# connector.net
KiCad netlist of a schematic drawn in Altium Designer
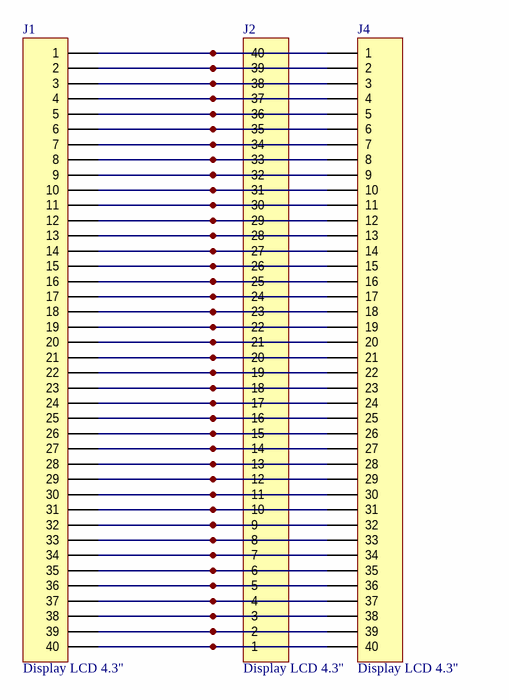
[diagram p0: connector.SchDoc]

(export (version "E")
  (design (tool "Eeschema 10.0.6"))
  (components
    (comp (ref "J1")
      (value "Display LCD 4.3''")
      (footprint "fcc-zif_40pin_0.5mm")
      (description "40-pin, 0.5mm, SMT, ZIF, Horizontal, Top Contact (WE 68714014022; Molex: 54104-4031)")
      (fields (field (name "PUBLISHER") "Altium Limited"))
      (libsource (lib "") (part "Header 40_1"))
    )
    (comp (ref "J2")
      (value "Display LCD 4.3''")
      (footprint "fcc-zif_40pin_0.5mm")
      (description "40-pin, 0.5mm, SMT, ZIF, Horizontal, Top Contact (WE 68714014022; Molex: 54104-4031)")
      (fields (field (name "PUBLISHER") "Altium Limited"))
      (libsource (lib "DEVELER_Library") (part "Header 40"))
    )
    (comp (ref "J4")
      (value "Display LCD 4.3''")
      (footprint "fcc-zif_40pin_0.5mm")
      (description "40-pin, 0.5mm, SMT, ZIF, Horizontal, Top Contact (WE 68714014022; Molex: 54104-4031)")
      (fields (field (name "PUBLISHER") "Altium Limited"))
      (libsource (lib "") (part "Header 40_2"))
    )
  )
  (nets
    (net (code "1") (name "Net-(J1-Pad1)") (class "Default")
      (node (ref "J1") (pin "1") (pinfunction "1_1") (pintype "passive"))
      (node (ref "J2") (pin "40") (pinfunction "40_40") (pintype "passive"))
      (node (ref "J4") (pin "1") (pinfunction "1_1") (pintype "passive"))
    )
    (net (code "2") (name "Net-(J1-Pad2)") (class "Default")
      (node (ref "J1") (pin "2") (pinfunction "2_2") (pintype "passive"))
      (node (ref "J2") (pin "39") (pinfunction "39_39") (pintype "passive"))
      (node (ref "J4") (pin "2") (pinfunction "2_2") (pintype "passive"))
    )
    (net (code "3") (name "Net-(J1-Pad3)") (class "Default")
      (node (ref "J1") (pin "3") (pinfunction "3_3") (pintype "passive"))
      (node (ref "J2") (pin "38") (pinfunction "38_38") (pintype "passive"))
      (node (ref "J4") (pin "3") (pinfunction "3_3") (pintype "passive"))
    )
    (net (code "4") (name "Net-(J1-Pad4)") (class "Default")
      (node (ref "J1") (pin "4") (pinfunction "4_4") (pintype "passive"))
      (node (ref "J2") (pin "37") (pinfunction "37_37") (pintype "passive"))
      (node (ref "J4") (pin "4") (pinfunction "4_4") (pintype "passive"))
    )
    (net (code "5") (name "Net-(J1-Pad5)") (class "Default")
      (node (ref "J1") (pin "5") (pinfunction "5_5") (pintype "passive"))
      (node (ref "J2") (pin "36") (pinfunction "36_36") (pintype "passive"))
      (node (ref "J4") (pin "5") (pinfunction "5_5") (pintype "passive"))
    )
    (net (code "6") (name "Net-(J1-Pad6)") (class "Default")
      (node (ref "J1") (pin "6") (pinfunction "6_6") (pintype "passive"))
      (node (ref "J2") (pin "35") (pinfunction "35_35") (pintype "passive"))
      (node (ref "J4") (pin "6") (pinfunction "6_6") (pintype "passive"))
    )
    (net (code "7") (name "Net-(J1-Pad7)") (class "Default")
      (node (ref "J1") (pin "7") (pinfunction "7_7") (pintype "passive"))
      (node (ref "J2") (pin "34") (pinfunction "34_34") (pintype "passive"))
      (node (ref "J4") (pin "7") (pinfunction "7_7") (pintype "passive"))
    )
    (net (code "8") (name "Net-(J1-Pad8)") (class "Default")
      (node (ref "J1") (pin "8") (pinfunction "8_8") (pintype "passive"))
      (node (ref "J2") (pin "33") (pinfunction "33_33") (pintype "passive"))
      (node (ref "J4") (pin "8") (pinfunction "8_8") (pintype "passive"))
    )
    (net (code "9") (name "Net-(J1-Pad9)") (class "Default")
      (node (ref "J1") (pin "9") (pinfunction "9_9") (pintype "passive"))
      (node (ref "J2") (pin "32") (pinfunction "32_32") (pintype "passive"))
      (node (ref "J4") (pin "9") (pinfunction "9_9") (pintype "passive"))
    )
    (net (code "10") (name "Net-(J1-Pad10)") (class "Default")
      (node (ref "J1") (pin "10") (pinfunction "10_10") (pintype "passive"))
      (node (ref "J2") (pin "31") (pinfunction "31_31") (pintype "passive"))
      (node (ref "J4") (pin "10") (pinfunction "10_10") (pintype "passive"))
    )
    (net (code "11") (name "Net-(J1-Pad11)") (class "Default")
      (node (ref "J1") (pin "11") (pinfunction "11_11") (pintype "passive"))
      (node (ref "J2") (pin "30") (pinfunction "30_30") (pintype "passive"))
      (node (ref "J4") (pin "11") (pinfunction "11_11") (pintype "passive"))
    )
    (net (code "12") (name "Net-(J1-Pad12)") (class "Default")
      (node (ref "J1") (pin "12") (pinfunction "12_12") (pintype "passive"))
      (node (ref "J2") (pin "29") (pinfunction "29_29") (pintype "passive"))
      (node (ref "J4") (pin "12") (pinfunction "12_12") (pintype "passive"))
    )
    (net (code "13") (name "Net-(J1-Pad13)") (class "Default")
      (node (ref "J1") (pin "13") (pinfunction "13_13") (pintype "passive"))
      (node (ref "J2") (pin "28") (pinfunction "28_28") (pintype "passive"))
      (node (ref "J4") (pin "13") (pinfunction "13_13") (pintype "passive"))
    )
    (net (code "14") (name "Net-(J1-Pad14)") (class "Default")
      (node (ref "J1") (pin "14") (pinfunction "14_14") (pintype "passive"))
      (node (ref "J2") (pin "27") (pinfunction "27_27") (pintype "passive"))
      (node (ref "J4") (pin "14") (pinfunction "14_14") (pintype "passive"))
    )
    (net (code "15") (name "Net-(J1-Pad15)") (class "Default")
      (node (ref "J1") (pin "15") (pinfunction "15_15") (pintype "passive"))
      (node (ref "J2") (pin "26") (pinfunction "26_26") (pintype "passive"))
      (node (ref "J4") (pin "15") (pinfunction "15_15") (pintype "passive"))
    )
    (net (code "16") (name "Net-(J1-Pad16)") (class "Default")
      (node (ref "J1") (pin "16") (pinfunction "16_16") (pintype "passive"))
      (node (ref "J2") (pin "25") (pinfunction "25_25") (pintype "passive"))
      (node (ref "J4") (pin "16") (pinfunction "16_16") (pintype "passive"))
    )
    (net (code "17") (name "Net-(J1-Pad17)") (class "Default")
      (node (ref "J1") (pin "17") (pinfunction "17_17") (pintype "passive"))
      (node (ref "J2") (pin "24") (pinfunction "24_24") (pintype "passive"))
      (node (ref "J4") (pin "17") (pinfunction "17_17") (pintype "passive"))
    )
    (net (code "18") (name "Net-(J1-Pad18)") (class "Default")
      (node (ref "J1") (pin "18") (pinfunction "18_18") (pintype "passive"))
      (node (ref "J2") (pin "23") (pinfunction "23_23") (pintype "passive"))
      (node (ref "J4") (pin "18") (pinfunction "18_18") (pintype "passive"))
    )
    (net (code "19") (name "Net-(J1-Pad19)") (class "Default")
      (node (ref "J1") (pin "19") (pinfunction "19_19") (pintype "passive"))
      (node (ref "J2") (pin "22") (pinfunction "22_22") (pintype "passive"))
      (node (ref "J4") (pin "19") (pinfunction "19_19") (pintype "passive"))
    )
    (net (code "20") (name "Net-(J1-Pad20)") (class "Default")
      (node (ref "J1") (pin "20") (pinfunction "20_20") (pintype "passive"))
      (node (ref "J2") (pin "21") (pinfunction "21_21") (pintype "passive"))
      (node (ref "J4") (pin "20") (pinfunction "20_20") (pintype "passive"))
    )
    (net (code "21") (name "Net-(J1-Pad21)") (class "Default")
      (node (ref "J1") (pin "21") (pinfunction "21_21") (pintype "passive"))
      (node (ref "J2") (pin "20") (pinfunction "20_20") (pintype "passive"))
      (node (ref "J4") (pin "21") (pinfunction "21_21") (pintype "passive"))
    )
    (net (code "22") (name "Net-(J1-Pad22)") (class "Default")
      (node (ref "J1") (pin "22") (pinfunction "22_22") (pintype "passive"))
      (node (ref "J2") (pin "19") (pinfunction "19_19") (pintype "passive"))
      (node (ref "J4") (pin "22") (pinfunction "22_22") (pintype "passive"))
    )
    (net (code "23") (name "Net-(J1-Pad23)") (class "Default")
      (node (ref "J1") (pin "23") (pinfunction "23_23") (pintype "passive"))
      (node (ref "J2") (pin "18") (pinfunction "18_18") (pintype "passive"))
      (node (ref "J4") (pin "23") (pinfunction "23_23") (pintype "passive"))
    )
    (net (code "24") (name "Net-(J1-Pad24)") (class "Default")
      (node (ref "J1") (pin "24") (pinfunction "24_24") (pintype "passive"))
      (node (ref "J2") (pin "17") (pinfunction "17_17") (pintype "passive"))
      (node (ref "J4") (pin "24") (pinfunction "24_24") (pintype "passive"))
    )
    (net (code "25") (name "Net-(J1-Pad25)") (class "Default")
      (node (ref "J1") (pin "25") (pinfunction "25_25") (pintype "passive"))
      (node (ref "J2") (pin "16") (pinfunction "16_16") (pintype "passive"))
      (node (ref "J4") (pin "25") (pinfunction "25_25") (pintype "passive"))
    )
    (net (code "26") (name "Net-(J1-Pad26)") (class "Default")
      (node (ref "J1") (pin "26") (pinfunction "26_26") (pintype "passive"))
      (node (ref "J2") (pin "15") (pinfunction "15_15") (pintype "passive"))
      (node (ref "J4") (pin "26") (pinfunction "26_26") (pintype "passive"))
    )
    (net (code "27") (name "Net-(J1-Pad27)") (class "Default")
      (node (ref "J1") (pin "27") (pinfunction "27_27") (pintype "passive"))
      (node (ref "J2") (pin "14") (pinfunction "14_14") (pintype "passive"))
      (node (ref "J4") (pin "27") (pinfunction "27_27") (pintype "passive"))
    )
    (net (code "28") (name "Net-(J1-Pad28)") (class "Default")
      (node (ref "J1") (pin "28") (pinfunction "28_28") (pintype "passive"))
      (node (ref "J2") (pin "13") (pinfunction "13_13") (pintype "passive"))
      (node (ref "J4") (pin "28") (pinfunction "28_28") (pintype "passive"))
    )
    (net (code "29") (name "Net-(J1-Pad29)") (class "Default")
      (node (ref "J1") (pin "29") (pinfunction "29_29") (pintype "passive"))
      (node (ref "J2") (pin "12") (pinfunction "12_12") (pintype "passive"))
      (node (ref "J4") (pin "29") (pinfunction "29_29") (pintype "passive"))
    )
    (net (code "30") (name "Net-(J1-Pad30)") (class "Default")
      (node (ref "J1") (pin "30") (pinfunction "30_30") (pintype "passive"))
      (node (ref "J2") (pin "11") (pinfunction "11_11") (pintype "passive"))
      (node (ref "J4") (pin "30") (pinfunction "30_30") (pintype "passive"))
    )
    (net (code "31") (name "Net-(J1-Pad31)") (class "Default")
      (node (ref "J1") (pin "31") (pinfunction "31_31") (pintype "passive"))
      (node (ref "J2") (pin "10") (pinfunction "10_10") (pintype "passive"))
      (node (ref "J4") (pin "31") (pinfunction "31_31") (pintype "passive"))
    )
    (net (code "32") (name "Net-(J1-Pad32)") (class "Default")
      (node (ref "J1") (pin "32") (pinfunction "32_32") (pintype "passive"))
      (node (ref "J2") (pin "9") (pinfunction "9_9") (pintype "passive"))
      (node (ref "J4") (pin "32") (pinfunction "32_32") (pintype "passive"))
    )
    (net (code "33") (name "Net-(J1-Pad33)") (class "Default")
      (node (ref "J1") (pin "33") (pinfunction "33_33") (pintype "passive"))
      (node (ref "J2") (pin "8") (pinfunction "8_8") (pintype "passive"))
      (node (ref "J4") (pin "33") (pinfunction "33_33") (pintype "passive"))
    )
    (net (code "34") (name "Net-(J1-Pad34)") (class "Default")
      (node (ref "J1") (pin "34") (pinfunction "34_34") (pintype "passive"))
      (node (ref "J2") (pin "7") (pinfunction "7_7") (pintype "passive"))
      (node (ref "J4") (pin "34") (pinfunction "34_34") (pintype "passive"))
    )
    (net (code "35") (name "Net-(J1-Pad35)") (class "Default")
      (node (ref "J1") (pin "35") (pinfunction "35_35") (pintype "passive"))
      (node (ref "J2") (pin "6") (pinfunction "6_6") (pintype "passive"))
      (node (ref "J4") (pin "35") (pinfunction "35_35") (pintype "passive"))
    )
    (net (code "36") (name "Net-(J1-Pad36)") (class "Default")
      (node (ref "J1") (pin "36") (pinfunction "36_36") (pintype "passive"))
      (node (ref "J2") (pin "5") (pinfunction "5_5") (pintype "passive"))
      (node (ref "J4") (pin "36") (pinfunction "36_36") (pintype "passive"))
    )
    (net (code "37") (name "Net-(J1-Pad37)") (class "Default")
      (node (ref "J1") (pin "37") (pinfunction "37_37") (pintype "passive"))
      (node (ref "J2") (pin "4") (pinfunction "4_4") (pintype "passive"))
      (node (ref "J4") (pin "37") (pinfunction "37_37") (pintype "passive"))
    )
    (net (code "38") (name "Net-(J1-Pad38)") (class "Default")
      (node (ref "J1") (pin "38") (pinfunction "38_38") (pintype "passive"))
      (node (ref "J2") (pin "3") (pinfunction "3_3") (pintype "passive"))
      (node (ref "J4") (pin "38") (pinfunction "38_38") (pintype "passive"))
    )
    (net (code "39") (name "Net-(J1-Pad39)") (class "Default")
      (node (ref "J1") (pin "39") (pinfunction "39_39") (pintype "passive"))
      (node (ref "J2") (pin "2") (pinfunction "2_2") (pintype "passive"))
      (node (ref "J4") (pin "39") (pinfunction "39_39") (pintype "passive"))
    )
    (net (code "40") (name "Net-(J1-Pad40)") (class "Default")
      (node (ref "J1") (pin "40") (pinfunction "40_40") (pintype "passive"))
      (node (ref "J2") (pin "1") (pinfunction "1_1") (pintype "passive"))
      (node (ref "J4") (pin "40") (pinfunction "40_40") (pintype "passive"))
    )
  )
)
